# 5V_3_3V__-2_5V_PowerSupply.net
KiCad netlist of a schematic drawn in EAGLE
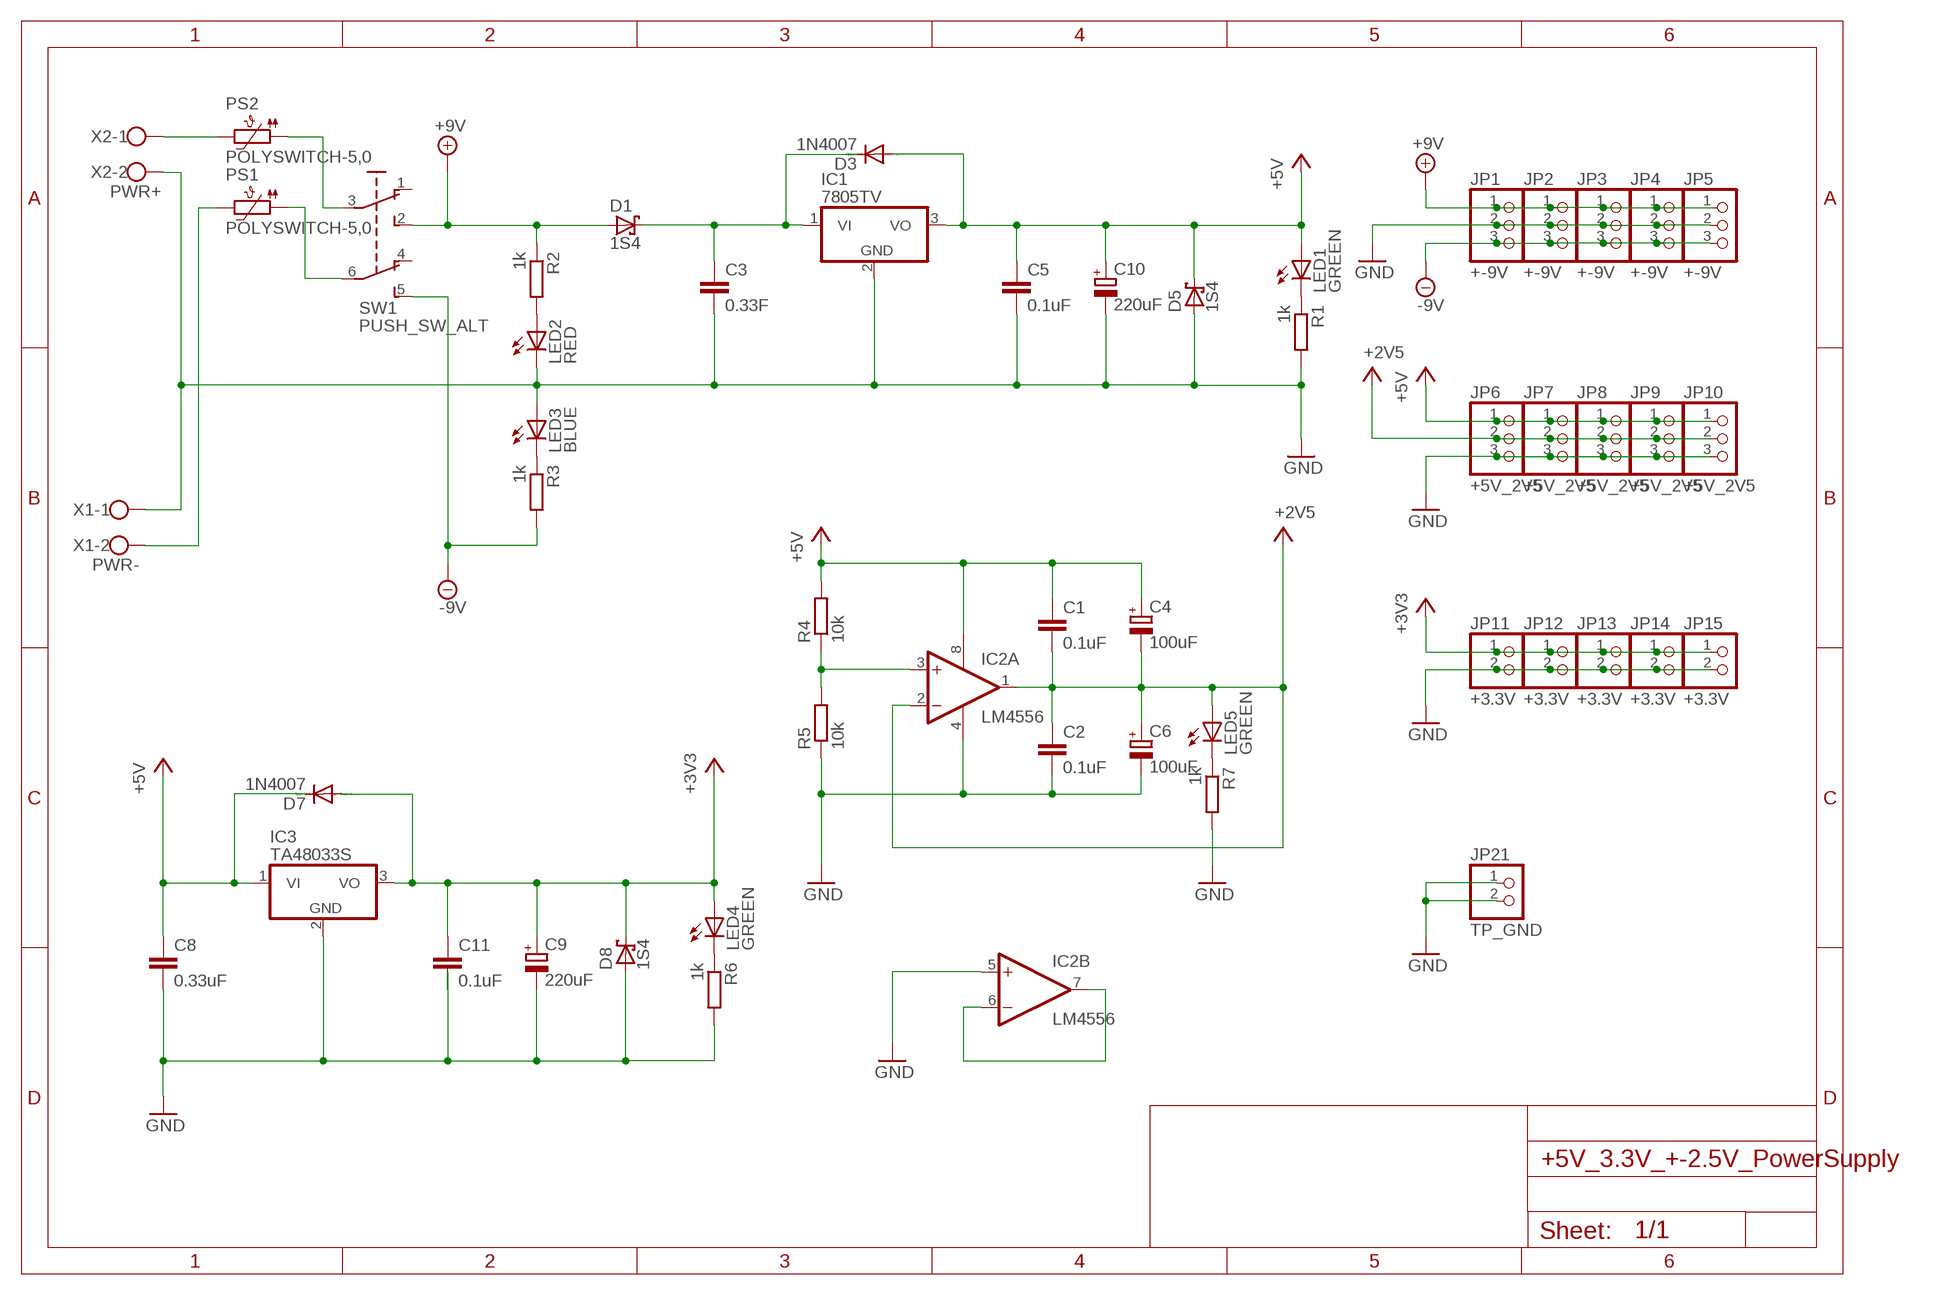
[diagram p0: schematic, sheet 1]

(export (version "E")
  (design (tool "Eeschema 10.0.6"))
  (components
    (comp (ref "C1")
      (value "0.1uF")
      (footprint "eagle-import:C025-024X044")
      (libsource (lib "eagle-import") (part "C-EU025-024X044"))
    )
    (comp (ref "C2")
      (value "0.1uF")
      (footprint "eagle-import:C025-024X044")
      (libsource (lib "eagle-import") (part "C-EU025-024X044"))
    )
    (comp (ref "C3")
      (value "0.33F")
      (footprint "eagle-import:C050-025X075")
      (libsource (lib "eagle-import") (part "C-EU050-025X075"))
    )
    (comp (ref "C4")
      (value "100uF")
      (footprint "eagle-import:E2,5-6")
      (libsource (lib "eagle-import") (part "CPOL-EUE2.5-6"))
    )
    (comp (ref "C5")
      (value "0.1uF")
      (footprint "eagle-import:C025-024X044")
      (libsource (lib "eagle-import") (part "C-EU025-024X044"))
    )
    (comp (ref "C6")
      (value "100uF")
      (footprint "eagle-import:E2,5-6")
      (libsource (lib "eagle-import") (part "CPOL-EUE2.5-6"))
    )
    (comp (ref "C8")
      (value "0.33uF")
      (footprint "eagle-import:C050-025X075")
      (libsource (lib "eagle-import") (part "C-EU050-025X075"))
    )
    (comp (ref "C9")
      (value "220uF")
      (footprint "eagle-import:E2,5-7")
      (libsource (lib "eagle-import") (part "CPOL-EUE2.5-7"))
    )
    (comp (ref "C10")
      (value "220uF")
      (footprint "eagle-import:E2,5-7")
      (libsource (lib "eagle-import") (part "CPOL-EUE2.5-7"))
    )
    (comp (ref "C11")
      (value "0.1uF")
      (footprint "eagle-import:C025-024X044")
      (libsource (lib "eagle-import") (part "C-EU025-024X044"))
    )
    (comp (ref "D1")
      (value "1S4")
      (footprint "eagle-import:DO35-7")
      (libsource (lib "eagle-import") (part "SCHOTTKY-DIODEDO35-7"))
    )
    (comp (ref "D3")
      (value "1N4007")
      (footprint "eagle-import:D-7.5")
      (libsource (lib "eagle-import") (part "DIODE-D-7.5"))
    )
    (comp (ref "D5")
      (value "1S4")
      (footprint "eagle-import:DO35-7")
      (libsource (lib "eagle-import") (part "SCHOTTKY-DIODEDO35-7"))
    )
    (comp (ref "D7")
      (value "1N4007")
      (footprint "eagle-import:D-7.5")
      (libsource (lib "eagle-import") (part "DIODE-D-7.5"))
    )
    (comp (ref "D8")
      (value "1S4")
      (footprint "eagle-import:DO35-7")
      (libsource (lib "eagle-import") (part "SCHOTTKY-DIODEDO35-7"))
    )
    (comp (ref "IC1")
      (value "7805TV")
      (footprint "eagle-import:TO220V")
      (libsource (lib "eagle-import") (part "78TV05"))
    )
    (comp (ref "IC2")
      (value "LM4556")
      (footprint "eagle-import:DIL08")
      (libsource (lib "eagle-import") (part "4558NLM"))
    )
    (comp (ref "IC3")
      (value "TA48033S")
      (footprint "eagle-import:TO220V")
      (libsource (lib "eagle-import") (part "78TV05"))
    )
    (comp (ref "JP1")
      (value "+-9V")
      (footprint "eagle-import:1X03")
      (libsource (lib "eagle-import") (part "PINHD-1X3"))
    )
    (comp (ref "JP2")
      (value "+-9V")
      (footprint "eagle-import:1X03")
      (libsource (lib "eagle-import") (part "PINHD-1X3"))
    )
    (comp (ref "JP3")
      (value "+-9V")
      (footprint "eagle-import:1X03")
      (libsource (lib "eagle-import") (part "PINHD-1X3"))
    )
    (comp (ref "JP4")
      (value "+-9V")
      (footprint "eagle-import:1X03")
      (libsource (lib "eagle-import") (part "PINHD-1X3"))
    )
    (comp (ref "JP5")
      (value "+-9V")
      (footprint "eagle-import:1X03")
      (libsource (lib "eagle-import") (part "PINHD-1X3"))
    )
    (comp (ref "JP6")
      (value "+5V_2V5")
      (footprint "eagle-import:1X03")
      (libsource (lib "eagle-import") (part "PINHD-1X3"))
    )
    (comp (ref "JP7")
      (value "+5V_2V5")
      (footprint "eagle-import:1X03")
      (libsource (lib "eagle-import") (part "PINHD-1X3"))
    )
    (comp (ref "JP8")
      (value "+5V_2V5")
      (footprint "eagle-import:1X03")
      (libsource (lib "eagle-import") (part "PINHD-1X3"))
    )
    (comp (ref "JP9")
      (value "+5V_2V5")
      (footprint "eagle-import:1X03")
      (libsource (lib "eagle-import") (part "PINHD-1X3"))
    )
    (comp (ref "JP10")
      (value "+5V_2V5")
      (footprint "eagle-import:1X03")
      (libsource (lib "eagle-import") (part "PINHD-1X3"))
    )
    (comp (ref "JP11")
      (value "+3.3V")
      (footprint "eagle-import:1X02")
      (libsource (lib "eagle-import") (part "PINHD-1X2"))
    )
    (comp (ref "JP12")
      (value "+3.3V")
      (footprint "eagle-import:1X02")
      (libsource (lib "eagle-import") (part "PINHD-1X2"))
    )
    (comp (ref "JP13")
      (value "+3.3V")
      (footprint "eagle-import:1X02")
      (libsource (lib "eagle-import") (part "PINHD-1X2"))
    )
    (comp (ref "JP14")
      (value "+3.3V")
      (footprint "eagle-import:1X02")
      (libsource (lib "eagle-import") (part "PINHD-1X2"))
    )
    (comp (ref "JP15")
      (value "+3.3V")
      (footprint "eagle-import:1X02")
      (libsource (lib "eagle-import") (part "PINHD-1X2"))
    )
    (comp (ref "JP21")
      (value "TP_GND")
      (footprint "eagle-import:1X02")
      (libsource (lib "eagle-import") (part "PINHD-1X2"))
    )
    (comp (ref "LED1")
      (value "GREEN")
      (footprint "eagle-import:LED3MM")
      (libsource (lib "eagle-import") (part "LED3MM"))
    )
    (comp (ref "LED2")
      (value "RED")
      (footprint "eagle-import:LED3MM")
      (libsource (lib "eagle-import") (part "LED3MM"))
    )
    (comp (ref "LED3")
      (value "BLUE")
      (footprint "eagle-import:LED3MM")
      (libsource (lib "eagle-import") (part "LED3MM"))
    )
    (comp (ref "LED4")
      (value "GREEN")
      (footprint "eagle-import:LED3MM")
      (libsource (lib "eagle-import") (part "LED3MM"))
    )
    (comp (ref "LED5")
      (value "GREEN")
      (footprint "eagle-import:LED3MM")
      (libsource (lib "eagle-import") (part "LED3MM"))
    )
    (comp (ref "PS1")
      (value "POLYSWITCH-5,0")
      (footprint "eagle-import:POLYSWITCH-5,0")
      (libsource (lib "eagle-import") (part "POLYSWITCH-5,0"))
    )
    (comp (ref "PS2")
      (value "POLYSWITCH-5,0")
      (footprint "eagle-import:POLYSWITCH-5,0")
      (libsource (lib "eagle-import") (part "POLYSWITCH-5,0"))
    )
    (comp (ref "R1")
      (value "1k")
      (footprint "eagle-import:0207_7")
      (libsource (lib "eagle-import") (part "R-EU_0207/7"))
    )
    (comp (ref "R2")
      (value "1k")
      (footprint "eagle-import:0207_7")
      (libsource (lib "eagle-import") (part "R-EU_0207/7"))
    )
    (comp (ref "R3")
      (value "1k")
      (footprint "eagle-import:0207_7")
      (libsource (lib "eagle-import") (part "R-EU_0207/7"))
    )
    (comp (ref "R4")
      (value "10k")
      (footprint "eagle-import:0207_7")
      (libsource (lib "eagle-import") (part "R-EU_0207/7"))
    )
    (comp (ref "R5")
      (value "10k")
      (footprint "eagle-import:0207_7")
      (libsource (lib "eagle-import") (part "R-EU_0207/7"))
    )
    (comp (ref "R6")
      (value "1k")
      (footprint "eagle-import:0207_7")
      (libsource (lib "eagle-import") (part "R-EU_0207/7"))
    )
    (comp (ref "R7")
      (value "1k")
      (footprint "eagle-import:0207_7")
      (libsource (lib "eagle-import") (part "R-EU_0207/7"))
    )
    (comp (ref "SW1")
      (value "PUSH_SW_ALT")
      (footprint "eagle-import:PUSH_SW_ALT")
      (libsource (lib "eagle-import") (part "PUSH_SW_ALT"))
    )
    (comp (ref "X1")
      (value "PWR-")
      (footprint "eagle-import:W237-102")
      (fields (field (name "MPN") "237-102"))
      (libsource (lib "eagle-import") (part "W237-102"))
    )
    (comp (ref "X2")
      (value "PWR+")
      (footprint "eagle-import:W237-102")
      (fields (field (name "MPN") "237-102"))
      (libsource (lib "eagle-import") (part "W237-102"))
    )
  )
  (nets
    (net (code "1") (name "+2V5") (class "Default")
      (node (ref "C1") (pin "2") (pinfunction "2_2") (pintype "passive"))
      (node (ref "C2") (pin "1") (pinfunction "1_1") (pintype "passive"))
      (node (ref "C4") (pin "-") (pinfunction "-_-") (pintype "passive"))
      (node (ref "C6") (pin "+") (pinfunction "+_+") (pintype "passive"))
      (node (ref "IC2") (pin "1") (pinfunction "OUT_1") (pintype "output"))
      (node (ref "IC2") (pin "2") (pinfunction "-IN_2") (pintype "input"))
      (node (ref "JP10") (pin "2") (pinfunction "2_2") (pintype "passive"))
      (node (ref "JP6") (pin "2") (pinfunction "2_2") (pintype "passive"))
      (node (ref "JP7") (pin "2") (pinfunction "2_2") (pintype "passive"))
      (node (ref "JP8") (pin "2") (pinfunction "2_2") (pintype "passive"))
      (node (ref "JP9") (pin "2") (pinfunction "2_2") (pintype "passive"))
      (node (ref "LED5") (pin "A") (pinfunction "A_A") (pintype "passive"))
    )
    (net (code "2") (name "+3V3") (class "Default")
      (node (ref "C11") (pin "1") (pinfunction "1_1") (pintype "passive"))
      (node (ref "C9") (pin "+") (pinfunction "+_+") (pintype "passive"))
      (node (ref "D7") (pin "A") (pinfunction "A_A") (pintype "passive"))
      (node (ref "D8") (pin "C") (pinfunction "C_C") (pintype "passive"))
      (node (ref "IC3") (pin "3") (pinfunction "VO_3") (pintype "passive"))
      (node (ref "JP11") (pin "1") (pinfunction "1_1") (pintype "passive"))
      (node (ref "JP12") (pin "1") (pinfunction "1_1") (pintype "passive"))
      (node (ref "JP13") (pin "1") (pinfunction "1_1") (pintype "passive"))
      (node (ref "JP14") (pin "1") (pinfunction "1_1") (pintype "passive"))
      (node (ref "JP15") (pin "1") (pinfunction "1_1") (pintype "passive"))
      (node (ref "LED4") (pin "A") (pinfunction "A_A") (pintype "passive"))
    )
    (net (code "3") (name "+5V") (class "Default")
      (node (ref "C1") (pin "1") (pinfunction "1_1") (pintype "passive"))
      (node (ref "C10") (pin "+") (pinfunction "+_+") (pintype "passive"))
      (node (ref "C4") (pin "+") (pinfunction "+_+") (pintype "passive"))
      (node (ref "C5") (pin "1") (pinfunction "1_1") (pintype "passive"))
      (node (ref "C8") (pin "1") (pinfunction "1_1") (pintype "passive"))
      (node (ref "D3") (pin "A") (pinfunction "A_A") (pintype "passive"))
      (node (ref "D5") (pin "C") (pinfunction "C_C") (pintype "passive"))
      (node (ref "D7") (pin "C") (pinfunction "C_C") (pintype "passive"))
      (node (ref "IC1") (pin "3") (pinfunction "VO_3") (pintype "passive"))
      (node (ref "IC2") (pin "8") (pinfunction "V+_8") (pintype "power_in"))
      (node (ref "IC3") (pin "1") (pinfunction "VI_1") (pintype "input"))
      (node (ref "JP10") (pin "1") (pinfunction "1_1") (pintype "passive"))
      (node (ref "JP6") (pin "1") (pinfunction "1_1") (pintype "passive"))
      (node (ref "JP7") (pin "1") (pinfunction "1_1") (pintype "passive"))
      (node (ref "JP8") (pin "1") (pinfunction "1_1") (pintype "passive"))
      (node (ref "JP9") (pin "1") (pinfunction "1_1") (pintype "passive"))
      (node (ref "LED1") (pin "A") (pinfunction "A_A") (pintype "passive"))
      (node (ref "R4") (pin "2") (pinfunction "2_2") (pintype "passive"))
    )
    (net (code "4") (name "+9V") (class "Default")
      (node (ref "D1") (pin "A") (pinfunction "A_A") (pintype "passive"))
      (node (ref "JP1") (pin "1") (pinfunction "1_1") (pintype "passive"))
      (node (ref "JP2") (pin "1") (pinfunction "1_1") (pintype "passive"))
      (node (ref "JP3") (pin "1") (pinfunction "1_1") (pintype "passive"))
      (node (ref "JP4") (pin "1") (pinfunction "1_1") (pintype "passive"))
      (node (ref "JP5") (pin "1") (pinfunction "1_1") (pintype "passive"))
      (node (ref "R2") (pin "1") (pinfunction "1_1") (pintype "passive"))
      (node (ref "SW1") (pin "2") (pinfunction "S_2") (pintype "passive"))
    )
    (net (code "5") (name "-9V") (class "Default")
      (node (ref "JP1") (pin "3") (pinfunction "3_3") (pintype "passive"))
      (node (ref "JP2") (pin "3") (pinfunction "3_3") (pintype "passive"))
      (node (ref "JP3") (pin "3") (pinfunction "3_3") (pintype "passive"))
      (node (ref "JP4") (pin "3") (pinfunction "3_3") (pintype "passive"))
      (node (ref "JP5") (pin "3") (pinfunction "3_3") (pintype "passive"))
      (node (ref "R3") (pin "2") (pinfunction "2_2") (pintype "passive"))
      (node (ref "SW1") (pin "5") (pinfunction "S1_5") (pintype "passive"))
    )
    (net (code "6") (name "GND") (class "Default")
      (node (ref "C10") (pin "-") (pinfunction "-_-") (pintype "passive"))
      (node (ref "C11") (pin "2") (pinfunction "2_2") (pintype "passive"))
      (node (ref "C2") (pin "2") (pinfunction "2_2") (pintype "passive"))
      (node (ref "C3") (pin "2") (pinfunction "2_2") (pintype "passive"))
      (node (ref "C5") (pin "2") (pinfunction "2_2") (pintype "passive"))
      (node (ref "C6") (pin "-") (pinfunction "-_-") (pintype "passive"))
      (node (ref "C8") (pin "2") (pinfunction "2_2") (pintype "passive"))
      (node (ref "C9") (pin "-") (pinfunction "-_-") (pintype "passive"))
      (node (ref "D5") (pin "A") (pinfunction "A_A") (pintype "passive"))
      (node (ref "D8") (pin "A") (pinfunction "A_A") (pintype "passive"))
      (node (ref "IC1") (pin "2") (pinfunction "GND_2") (pintype "passive"))
      (node (ref "IC2") (pin "4") (pinfunction "V-_4") (pintype "power_in"))
      (node (ref "IC2") (pin "5") (pinfunction "+IN_5") (pintype "input"))
      (node (ref "IC3") (pin "2") (pinfunction "GND_2") (pintype "passive"))
      (node (ref "JP1") (pin "2") (pinfunction "2_2") (pintype "passive"))
      (node (ref "JP10") (pin "3") (pinfunction "3_3") (pintype "passive"))
      (node (ref "JP11") (pin "2") (pinfunction "2_2") (pintype "passive"))
      (node (ref "JP12") (pin "2") (pinfunction "2_2") (pintype "passive"))
      (node (ref "JP13") (pin "2") (pinfunction "2_2") (pintype "passive"))
      (node (ref "JP14") (pin "2") (pinfunction "2_2") (pintype "passive"))
      (node (ref "JP15") (pin "2") (pinfunction "2_2") (pintype "passive"))
      (node (ref "JP2") (pin "2") (pinfunction "2_2") (pintype "passive"))
      (node (ref "JP21") (pin "1") (pinfunction "1_1") (pintype "passive"))
      (node (ref "JP21") (pin "2") (pinfunction "2_2") (pintype "passive"))
      (node (ref "JP3") (pin "2") (pinfunction "2_2") (pintype "passive"))
      (node (ref "JP4") (pin "2") (pinfunction "2_2") (pintype "passive"))
      (node (ref "JP5") (pin "2") (pinfunction "2_2") (pintype "passive"))
      (node (ref "JP6") (pin "3") (pinfunction "3_3") (pintype "passive"))
      (node (ref "JP7") (pin "3") (pinfunction "3_3") (pintype "passive"))
      (node (ref "JP8") (pin "3") (pinfunction "3_3") (pintype "passive"))
      (node (ref "JP9") (pin "3") (pinfunction "3_3") (pintype "passive"))
      (node (ref "LED2") (pin "K") (pinfunction "C_K") (pintype "passive"))
      (node (ref "LED3") (pin "A") (pinfunction "A_A") (pintype "passive"))
      (node (ref "R1") (pin "2") (pinfunction "2_2") (pintype "passive"))
      (node (ref "R5") (pin "1") (pinfunction "1_1") (pintype "passive"))
      (node (ref "R6") (pin "2") (pinfunction "2_2") (pintype "passive"))
      (node (ref "R7") (pin "2") (pinfunction "2_2") (pintype "passive"))
      (node (ref "X1") (pin "1") (pinfunction "KL_1") (pintype "passive"))
      (node (ref "X2") (pin "2") (pinfunction "KL_2") (pintype "passive"))
    )
    (net (code "7") (name "Net-(IC1-VI)") (class "Default")
      (node (ref "C3") (pin "1") (pinfunction "1_1") (pintype "passive"))
      (node (ref "D1") (pin "C") (pinfunction "C_C") (pintype "passive"))
      (node (ref "D3") (pin "C") (pinfunction "C_C") (pintype "passive"))
      (node (ref "IC1") (pin "1") (pinfunction "VI_1") (pintype "input"))
    )
    (net (code "8") (name "Net-(IC2A-+IN)") (class "Default")
      (node (ref "IC2") (pin "3") (pinfunction "+IN_3") (pintype "input"))
      (node (ref "R4") (pin "1") (pinfunction "1_1") (pintype "passive"))
      (node (ref "R5") (pin "2") (pinfunction "2_2") (pintype "passive"))
    )
    (net (code "9") (name "Net-(IC2B--IN)") (class "Default")
      (node (ref "IC2") (pin "6") (pinfunction "-IN_6") (pintype "input"))
      (node (ref "IC2") (pin "7") (pinfunction "OUT_7") (pintype "output"))
    )
    (net (code "10") (name "Net-(LED1-C)") (class "Default")
      (node (ref "LED1") (pin "K") (pinfunction "C_K") (pintype "passive"))
      (node (ref "R1") (pin "1") (pinfunction "1_1") (pintype "passive"))
    )
    (net (code "11") (name "Net-(LED2-PadA)") (class "Default")
      (node (ref "LED2") (pin "A") (pinfunction "A_A") (pintype "passive"))
      (node (ref "R2") (pin "2") (pinfunction "2_2") (pintype "passive"))
    )
    (net (code "12") (name "Net-(LED3-C)") (class "Default")
      (node (ref "LED3") (pin "K") (pinfunction "C_K") (pintype "passive"))
      (node (ref "R3") (pin "1") (pinfunction "1_1") (pintype "passive"))
    )
    (net (code "13") (name "Net-(LED4-C)") (class "Default")
      (node (ref "LED4") (pin "K") (pinfunction "C_K") (pintype "passive"))
      (node (ref "R6") (pin "1") (pinfunction "1_1") (pintype "passive"))
    )
    (net (code "14") (name "Net-(LED5-C)") (class "Default")
      (node (ref "LED5") (pin "K") (pinfunction "C_K") (pintype "passive"))
      (node (ref "R7") (pin "1") (pinfunction "1_1") (pintype "passive"))
    )
    (net (code "15") (name "Net-(SW1-P)") (class "Default")
      (node (ref "PS2") (pin "1") (pinfunction "1_1") (pintype "passive"))
      (node (ref "SW1") (pin "3") (pinfunction "P_3") (pintype "passive"))
    )
    (net (code "16") (name "Net-(SW1-P1)") (class "Default")
      (node (ref "PS1") (pin "1") (pinfunction "1_1") (pintype "passive"))
      (node (ref "SW1") (pin "6") (pinfunction "P1_6") (pintype "passive"))
    )
    (net (code "17") (name "Net-(X1B-KL)") (class "Default")
      (node (ref "PS1") (pin "2") (pinfunction "2_2") (pintype "passive"))
      (node (ref "X1") (pin "2") (pinfunction "KL_2") (pintype "passive"))
    )
    (net (code "18") (name "Net-(X2A-KL)") (class "Default")
      (node (ref "PS2") (pin "2") (pinfunction "2_2") (pintype "passive"))
      (node (ref "X2") (pin "1") (pinfunction "KL_1") (pintype "passive"))
    )
    (net (code "19") (name "unconnected-(SW1-O-Pad1)") (class "Default")
      (node (ref "SW1") (pin "1") (pinfunction "O_1") (pintype "passive"))
    )
    (net (code "20") (name "unconnected-(SW1-O1-Pad4)") (class "Default")
      (node (ref "SW1") (pin "4") (pinfunction "O1_4") (pintype "passive"))
    )
  )
)
